# 06-RTL8111H-1.net
KiCad netlist of a schematic drawn in Altium Designer
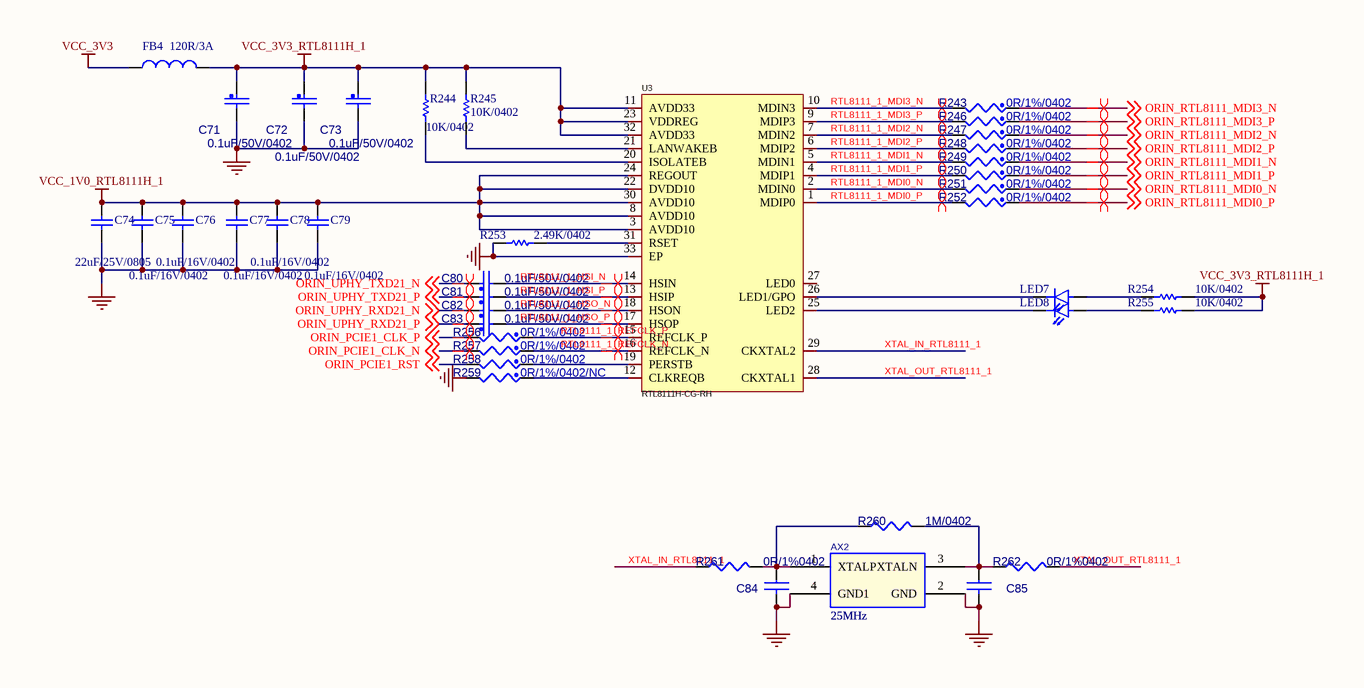
[diagram p0: 06-RTL8111H-1.schdoc]

(export (version "E")
  (design (tool "Eeschema 10.0.6"))
  (components
    (comp (ref "AX2")
      (value "25MHz")
      (footprint "2016")
      (fields (field (name "ALTIUM_VALUE") "25MHz"))
      (libsource (lib "*") (part "XTAL_0"))
    )
    (comp (ref "C71")
      (value "0.1uF/50V/0402")
      (footprint "C0402")
      (description "GCM155R71H104KE02/MURATA")
      (fields (field (name "TOLERANCE") "10%") (field (name "VOLTAGE") "16V"))
      (libsource (lib "*") (part "CAP_NP"))
    )
    (comp (ref "C72")
      (value "0.1uF/50V/0402")
      (footprint "C0402")
      (description "GCM155R71H104KE02/MURATA")
      (fields (field (name "TOLERANCE") "10%") (field (name "VOLTAGE") "16V"))
      (libsource (lib "*") (part "CAP_NP"))
    )
    (comp (ref "C73")
      (value "0.1uF/50V/0402")
      (footprint "C0402")
      (description "GCM155R71H104KE02/MURATA")
      (fields (field (name "TOLERANCE") "10%") (field (name "VOLTAGE") "16V"))
      (libsource (lib "*") (part "CAP_NP"))
    )
    (comp (ref "C74")
      (value "22uF/25V/0805")
      (description "Capacitor")
      (fields (field (name "PUBLISHER") "Altium Limited"))
      (libsource (lib "LIBS") (part "CAP"))
    )
    (comp (ref "C75")
      (value "0.1uF/16V/0402")
      (description "Capacitor")
      (fields (field (name "PUBLISHER") "Altium Limited"))
      (libsource (lib "LIBS") (part "CAP"))
    )
    (comp (ref "C76")
      (value "0.1uF/16V/0402")
      (description "Capacitor")
      (fields (field (name "PUBLISHER") "Altium Limited"))
      (libsource (lib "LIBS") (part "CAP"))
    )
    (comp (ref "C77")
      (value "0.1uF/16V/0402")
      (description "Capacitor")
      (fields (field (name "PUBLISHER") "Altium Limited"))
      (libsource (lib "LIBS") (part "CAP"))
    )
    (comp (ref "C78")
      (value "0.1uF/16V/0402")
      (description "Capacitor")
      (fields (field (name "PUBLISHER") "Altium Limited"))
      (libsource (lib "LIBS") (part "CAP"))
    )
    (comp (ref "C79")
      (value "0.1uF/16V/0402")
      (description "Capacitor")
      (fields (field (name "PUBLISHER") "Altium Limited"))
      (libsource (lib "LIBS") (part "CAP"))
    )
    (comp (ref "C80")
      (value "0.1uF/50V/0402")
      (footprint "C0402")
      (description "GCM155R71H104KE02/MURATA")
      (fields (field (name "TOLERANCE") "10%") (field (name "VOLTAGE") "16V"))
      (libsource (lib "*") (part "CAP_NP"))
    )
    (comp (ref "C81")
      (value "0.1uF/50V/0402")
      (footprint "C0402")
      (description "GCM155R71H104KE02/MURATA")
      (fields (field (name "TOLERANCE") "10%") (field (name "VOLTAGE") "16V"))
      (libsource (lib "*") (part "CAP_NP"))
    )
    (comp (ref "C82")
      (value "0.1uF/50V/0402")
      (footprint "C0402")
      (description "GCM155R71H104KE02/MURATA")
      (fields (field (name "TOLERANCE") "10%") (field (name "VOLTAGE") "16V"))
      (libsource (lib "*") (part "CAP_NP"))
    )
    (comp (ref "C83")
      (value "0.1uF/50V/0402")
      (footprint "C0402")
      (description "GCM155R71H104KE02/MURATA")
      (fields (field (name "TOLERANCE") "10%") (field (name "VOLTAGE") "16V"))
      (libsource (lib "*") (part "CAP_NP"))
    )
    (comp (ref "C84") (value "CAP NP_Dup3") (footprint "C0402") (libsource (lib "*") (part "CAP NP_Dup3")))
    (comp (ref "C85") (value "CAP NP_Dup3") (footprint "C0402") (libsource (lib "*") (part "CAP NP_Dup3")))
    (comp (ref "FB4")
      (value "120R/3A")
      (footprint "L0603")
      (description "BLM18KG121TN1D")
      (fields (field (name "PUBLISHER") "Altium Limited"))
      (libsource (lib "LIBS") (part "Inductor"))
    )
    (comp (ref "LED7") (value "LED_GREEN") (footprint "LED0603") (libsource (lib "LIBS") (part "LED")))
    (comp (ref "LED8") (value "LED_GREEN") (footprint "LED0603") (libsource (lib "LIBS") (part "LED")))
    (comp (ref "R243")
      (value "0R/1%/0402")
      (footprint "R0402")
      (description "AC0402FR-070RL/YAGEO")
      (fields (field (name "TOLERANCE") "1%") (field (name "Comment") "RES_Dup2"))
      (libsource (lib "*") (part "RES_Dup2"))
    )
    (comp (ref "R244")
      (value "10K/0402")
      (footprint "R0402")
      (description "Semiconductor Resistor")
      (fields (field (name "PUBLISHER") "Altium Limited"))
      (libsource (lib "LIBS") (part "Res Semi"))
    )
    (comp (ref "R245")
      (value "10K/0402")
      (footprint "R0402")
      (description "Semiconductor Resistor")
      (fields (field (name "PUBLISHER") "Altium Limited"))
      (libsource (lib "LIBS") (part "Res Semi"))
    )
    (comp (ref "R246")
      (value "0R/1%/0402")
      (footprint "R0402")
      (description "AC0402FR-070RL/YAGEO")
      (fields (field (name "TOLERANCE") "1%") (field (name "Comment") "RES_Dup2"))
      (libsource (lib "*") (part "RES_Dup2"))
    )
    (comp (ref "R247")
      (value "0R/1%/0402")
      (footprint "R0402")
      (description "AC0402FR-070RL/YAGEO")
      (fields (field (name "TOLERANCE") "1%") (field (name "Comment") "RES_Dup2"))
      (libsource (lib "*") (part "RES_Dup2"))
    )
    (comp (ref "R248")
      (value "0R/1%/0402")
      (footprint "R0402")
      (description "AC0402FR-070RL/YAGEO")
      (fields (field (name "TOLERANCE") "1%") (field (name "Comment") "RES_Dup2"))
      (libsource (lib "*") (part "RES_Dup2"))
    )
    (comp (ref "R249")
      (value "0R/1%/0402")
      (footprint "R0402")
      (description "AC0402FR-070RL/YAGEO")
      (fields (field (name "TOLERANCE") "1%") (field (name "Comment") "RES_Dup2"))
      (libsource (lib "*") (part "RES_Dup2"))
    )
    (comp (ref "R250")
      (value "0R/1%/0402")
      (footprint "R0402")
      (description "AC0402FR-070RL/YAGEO")
      (fields (field (name "TOLERANCE") "1%") (field (name "Comment") "RES_Dup2"))
      (libsource (lib "*") (part "RES_Dup2"))
    )
    (comp (ref "R251")
      (value "0R/1%/0402")
      (footprint "R0402")
      (description "AC0402FR-070RL/YAGEO")
      (fields (field (name "TOLERANCE") "1%") (field (name "Comment") "RES_Dup2"))
      (libsource (lib "*") (part "RES_Dup2"))
    )
    (comp (ref "R252")
      (value "0R/1%/0402")
      (footprint "R0402")
      (description "AC0402FR-070RL/YAGEO")
      (fields (field (name "TOLERANCE") "1%") (field (name "Comment") "RES_Dup2"))
      (libsource (lib "*") (part "RES_Dup2"))
    )
    (comp (ref "R253")
      (value "2.49K/0402")
      (footprint "R0402")
      (description "Semiconductor Resistor")
      (fields (field (name "PUBLISHER") "Altium Limited"))
      (libsource (lib "LIBS") (part "Res Semi"))
    )
    (comp (ref "R254")
      (value "10K/0402")
      (footprint "R0402")
      (description "Semiconductor Resistor")
      (fields (field (name "PUBLISHER") "Altium Limited"))
      (libsource (lib "LIBS") (part "Res Semi"))
    )
    (comp (ref "R255")
      (value "10K/0402")
      (footprint "R0402")
      (description "Semiconductor Resistor")
      (fields (field (name "PUBLISHER") "Altium Limited"))
      (libsource (lib "LIBS") (part "Res Semi"))
    )
    (comp (ref "R256")
      (value "0R/1%/0402")
      (footprint "R0402")
      (description "AC0402FR-070RL/YAGEO")
      (fields (field (name "TOLERANCE") "1%") (field (name "Comment") "RES_Dup2"))
      (libsource (lib "*") (part "RES_Dup2"))
    )
    (comp (ref "R257")
      (value "0R/1%/0402")
      (footprint "R0402")
      (description "AC0402FR-070RL/YAGEO")
      (fields (field (name "TOLERANCE") "1%") (field (name "Comment") "RES_Dup2"))
      (libsource (lib "*") (part "RES_Dup2"))
    )
    (comp (ref "R258")
      (value "0R/1%/0402")
      (footprint "R0402")
      (description "AC0402FR-070RL/YAGEO")
      (fields (field (name "TOLERANCE") "1%") (field (name "Comment") "RES_Dup2"))
      (libsource (lib "*") (part "RES_Dup2"))
    )
    (comp (ref "R259")
      (value "0R/1%/0402/NC")
      (footprint "R0402")
      (description "AC0402FR-070RL/YAGEO")
      (fields (field (name "TOLERANCE") "1%") (field (name "Comment") "RES_Dup2"))
      (libsource (lib "*") (part "RES_Dup2"))
    )
    (comp (ref "R260")
      (value "1M/0402")
      (footprint "R0402")
      (fields (field (name "Comment") "R_Dup3"))
      (libsource (lib "*") (part "R_Dup3"))
    )
    (comp (ref "R261")
      (value "0R/1%0402")
      (footprint "R0402")
      (fields (field (name "Comment") "R_Dup3"))
      (libsource (lib "*") (part "R_Dup3"))
    )
    (comp (ref "R262")
      (value "0R/1%0402")
      (footprint "R0402")
      (fields (field (name "Comment") "R_Dup3"))
      (libsource (lib "*") (part "R_Dup3"))
    )
    (comp (ref "U3")
      (value "RTL8111H-CG-RH")
      (footprint "RTL8111H-CG-RH")
      (fields (field (name "MANUFACTURER") "REALTEK(瑞昱)") (field (name "MANUFACTURER PART") "RTL8111H-CG"))
      (libsource (lib "17267508141_1726750814") (part "RTL8111H-CG"))
    )
  )
  (nets
    (net (code "1") (name "/RTL8111_1_HSI_N") (class "Default")
      (node (ref "C80") (pin "2") (pinfunction "2_2") (pintype "passive"))
      (node (ref "U3") (pin "14") (pinfunction "HSIN_14") (pintype "passive"))
    )
    (net (code "2") (name "/RTL8111_1_HSI_P") (class "Default")
      (node (ref "C81") (pin "2") (pinfunction "2_2") (pintype "passive"))
      (node (ref "U3") (pin "13") (pinfunction "HSIP_13") (pintype "passive"))
    )
    (net (code "3") (name "/RTL8111_1_HSO_N") (class "Default")
      (node (ref "C82") (pin "2") (pinfunction "2_2") (pintype "passive"))
      (node (ref "U3") (pin "18") (pinfunction "HSON_18") (pintype "passive"))
    )
    (net (code "4") (name "/RTL8111_1_HSO_P") (class "Default")
      (node (ref "C83") (pin "2") (pinfunction "2_2") (pintype "passive"))
      (node (ref "U3") (pin "17") (pinfunction "HSOP_17") (pintype "passive"))
    )
    (net (code "5") (name "/RTL8111_1_MDI0_N") (class "Default")
      (node (ref "R251") (pin "2") (pinfunction "2_2") (pintype "passive"))
      (node (ref "U3") (pin "2") (pinfunction "MDIN0_2") (pintype "passive"))
    )
    (net (code "6") (name "/RTL8111_1_MDI0_P") (class "Default")
      (node (ref "R252") (pin "2") (pinfunction "2_2") (pintype "passive"))
      (node (ref "U3") (pin "1") (pinfunction "MDIP0_1") (pintype "passive"))
    )
    (net (code "7") (name "/RTL8111_1_MDI1_N") (class "Default")
      (node (ref "R249") (pin "2") (pinfunction "2_2") (pintype "passive"))
      (node (ref "U3") (pin "5") (pinfunction "MDIN1_5") (pintype "passive"))
    )
    (net (code "8") (name "/RTL8111_1_MDI1_P") (class "Default")
      (node (ref "R250") (pin "2") (pinfunction "2_2") (pintype "passive"))
      (node (ref "U3") (pin "4") (pinfunction "MDIP1_4") (pintype "passive"))
    )
    (net (code "9") (name "/RTL8111_1_MDI2_N") (class "Default")
      (node (ref "R247") (pin "2") (pinfunction "2_2") (pintype "passive"))
      (node (ref "U3") (pin "7") (pinfunction "MDIN2_7") (pintype "passive"))
    )
    (net (code "10") (name "/RTL8111_1_MDI2_P") (class "Default")
      (node (ref "R248") (pin "2") (pinfunction "2_2") (pintype "passive"))
      (node (ref "U3") (pin "6") (pinfunction "MDIP2_6") (pintype "passive"))
    )
    (net (code "11") (name "/RTL8111_1_MDI3_N") (class "Default")
      (node (ref "R243") (pin "2") (pinfunction "2_2") (pintype "passive"))
      (node (ref "U3") (pin "10") (pinfunction "MDIN3_10") (pintype "passive"))
    )
    (net (code "12") (name "/RTL8111_1_MDI3_P") (class "Default")
      (node (ref "R246") (pin "2") (pinfunction "2_2") (pintype "passive"))
      (node (ref "U3") (pin "9") (pinfunction "MDIP3_9") (pintype "passive"))
    )
    (net (code "13") (name "/RTL8111_1_REFCLK_N") (class "Default")
      (node (ref "R257") (pin "1") (pinfunction "1_1") (pintype "passive"))
      (node (ref "U3") (pin "16") (pinfunction "REFCLK_N_16") (pintype "passive"))
    )
    (net (code "14") (name "/RTL8111_1_REFCLK_P") (class "Default")
      (node (ref "R256") (pin "1") (pinfunction "1_1") (pintype "passive"))
      (node (ref "U3") (pin "15") (pinfunction "REFCLK_P_15") (pintype "passive"))
    )
    (net (code "15") (name "/XTAL_IN_RTL8111_1") (class "Default")
      (node (ref "R261") (pin "1") (pinfunction "1_1") (pintype "passive"))
      (node (ref "U3") (pin "29") (pinfunction "CKXTAL2_29") (pintype "passive"))
    )
    (net (code "16") (name "/XTAL_OUT_RTL8111_1") (class "Default")
      (node (ref "R262") (pin "2") (pinfunction "2_2") (pintype "passive"))
      (node (ref "U3") (pin "28") (pinfunction "CKXTAL1_28") (pintype "passive"))
    )
    (net (code "17") (name "GND") (class "Default")
      (node (ref "AX2") (pin "2") (pinfunction "GND_2") (pintype "passive"))
      (node (ref "AX2") (pin "4") (pinfunction "GND1_4") (pintype "passive"))
      (node (ref "C71") (pin "2") (pinfunction "2_2") (pintype "passive"))
      (node (ref "C72") (pin "2") (pinfunction "2_2") (pintype "passive"))
      (node (ref "C73") (pin "2") (pinfunction "2_2") (pintype "passive"))
      (node (ref "C74") (pin "1") (pinfunction "1_1") (pintype "passive"))
      (node (ref "C75") (pin "1") (pinfunction "1_1") (pintype "passive"))
      (node (ref "C76") (pin "1") (pinfunction "1_1") (pintype "passive"))
      (node (ref "C77") (pin "1") (pinfunction "1_1") (pintype "passive"))
      (node (ref "C78") (pin "1") (pinfunction "1_1") (pintype "passive"))
      (node (ref "C79") (pin "1") (pinfunction "1_1") (pintype "passive"))
      (node (ref "C84") (pin "2") (pinfunction "2_2") (pintype "passive"))
      (node (ref "C85") (pin "2") (pinfunction "2_2") (pintype "passive"))
      (node (ref "R253") (pin "1") (pinfunction "1_1") (pintype "passive"))
      (node (ref "R259") (pin "2") (pinfunction "2_2") (pintype "passive"))
      (node (ref "U3") (pin "33") (pinfunction "EP_33") (pintype "passive"))
    )
    (net (code "18") (name "Net-(AX2-XTALN)") (class "Default")
      (node (ref "AX2") (pin "3") (pinfunction "XTALN_3") (pintype "passive"))
      (node (ref "C85") (pin "1") (pinfunction "1_1") (pintype "passive"))
      (node (ref "R260") (pin "2") (pinfunction "2_2") (pintype "passive"))
      (node (ref "R262") (pin "1") (pinfunction "1_1") (pintype "passive"))
    )
    (net (code "19") (name "Net-(AX2-XTALP)") (class "Default")
      (node (ref "AX2") (pin "1") (pinfunction "XTALP_1") (pintype "passive"))
      (node (ref "C84") (pin "1") (pinfunction "1_1") (pintype "passive"))
      (node (ref "R260") (pin "1") (pinfunction "1_1") (pintype "passive"))
      (node (ref "R261") (pin "2") (pinfunction "2_2") (pintype "passive"))
    )
    (net (code "20") (name "Net-(LED7-Pad1)") (class "Default")
      (node (ref "LED7") (pin "1") (pinfunction "1_1") (pintype "passive"))
      (node (ref "R254") (pin "2") (pinfunction "2_2") (pintype "passive"))
    )
    (net (code "21") (name "Net-(LED8-Pad1)") (class "Default")
      (node (ref "LED8") (pin "1") (pinfunction "1_1") (pintype "passive"))
      (node (ref "R255") (pin "2") (pinfunction "2_2") (pintype "passive"))
    )
    (net (code "22") (name "Net-(U3-CLKREQB)") (class "Default")
      (node (ref "R259") (pin "1") (pinfunction "1_1") (pintype "passive"))
      (node (ref "U3") (pin "12") (pinfunction "CLKREQB_12") (pintype "passive"))
    )
    (net (code "23") (name "Net-(U3-ISOLATEB)") (class "Default")
      (node (ref "R244") (pin "2") (pinfunction "2_2") (pintype "passive"))
      (node (ref "U3") (pin "20") (pinfunction "ISOLATEB_20") (pintype "passive"))
    )
    (net (code "24") (name "Net-(U3-LANWAKEB)") (class "Default")
      (node (ref "R245") (pin "2") (pinfunction "2_2") (pintype "passive"))
      (node (ref "U3") (pin "21") (pinfunction "LANWAKEB_21") (pintype "passive"))
    )
    (net (code "25") (name "Net-(U3-LED1{slash}GPO)") (class "Default")
      (node (ref "LED7") (pin "2") (pinfunction "2_2") (pintype "passive"))
      (node (ref "U3") (pin "26") (pinfunction "LED1/GPO_26") (pintype "passive"))
    )
    (net (code "26") (name "Net-(U3-LED2)") (class "Default")
      (node (ref "LED8") (pin "2") (pinfunction "2_2") (pintype "passive"))
      (node (ref "U3") (pin "25") (pinfunction "LED2_25") (pintype "passive"))
    )
    (net (code "27") (name "Net-(U3-PERSTB)") (class "Default")
      (node (ref "R258") (pin "1") (pinfunction "1_1") (pintype "passive"))
      (node (ref "U3") (pin "19") (pinfunction "PERSTB_19") (pintype "passive"))
    )
    (net (code "28") (name "Net-(U3-RSET)") (class "Default")
      (node (ref "R253") (pin "2") (pinfunction "2_2") (pintype "passive"))
      (node (ref "U3") (pin "31") (pinfunction "RSET_31") (pintype "passive"))
    )
    (net (code "29") (name "ORIN_PCIE1_CLK_N") (class "Default")
      (node (ref "R257") (pin "2") (pinfunction "2_2") (pintype "passive"))
    )
    (net (code "30") (name "ORIN_PCIE1_CLK_P") (class "Default")
      (node (ref "R256") (pin "2") (pinfunction "2_2") (pintype "passive"))
    )
    (net (code "31") (name "ORIN_PCIE1_RST") (class "Default")
      (node (ref "R258") (pin "2") (pinfunction "2_2") (pintype "passive"))
    )
    (net (code "32") (name "ORIN_RTL8111_MDI0_N") (class "Default")
      (node (ref "R251") (pin "1") (pinfunction "1_1") (pintype "passive"))
    )
    (net (code "33") (name "ORIN_RTL8111_MDI0_P") (class "Default")
      (node (ref "R252") (pin "1") (pinfunction "1_1") (pintype "passive"))
    )
    (net (code "34") (name "ORIN_RTL8111_MDI1_N") (class "Default")
      (node (ref "R249") (pin "1") (pinfunction "1_1") (pintype "passive"))
    )
    (net (code "35") (name "ORIN_RTL8111_MDI1_P") (class "Default")
      (node (ref "R250") (pin "1") (pinfunction "1_1") (pintype "passive"))
    )
    (net (code "36") (name "ORIN_RTL8111_MDI2_N") (class "Default")
      (node (ref "R247") (pin "1") (pinfunction "1_1") (pintype "passive"))
    )
    (net (code "37") (name "ORIN_RTL8111_MDI2_P") (class "Default")
      (node (ref "R248") (pin "1") (pinfunction "1_1") (pintype "passive"))
    )
    (net (code "38") (name "ORIN_RTL8111_MDI3_N") (class "Default")
      (node (ref "R243") (pin "1") (pinfunction "1_1") (pintype "passive"))
    )
    (net (code "39") (name "ORIN_RTL8111_MDI3_P") (class "Default")
      (node (ref "R246") (pin "1") (pinfunction "1_1") (pintype "passive"))
    )
    (net (code "40") (name "ORIN_UPHY_RXD21_N") (class "Default")
      (node (ref "C82") (pin "1") (pinfunction "1_1") (pintype "passive"))
    )
    (net (code "41") (name "ORIN_UPHY_RXD21_P") (class "Default")
      (node (ref "C83") (pin "1") (pinfunction "1_1") (pintype "passive"))
    )
    (net (code "42") (name "ORIN_UPHY_TXD21_N") (class "Default")
      (node (ref "C80") (pin "1") (pinfunction "1_1") (pintype "passive"))
    )
    (net (code "43") (name "ORIN_UPHY_TXD21_P") (class "Default")
      (node (ref "C81") (pin "1") (pinfunction "1_1") (pintype "passive"))
    )
    (net (code "44") (name "VCC_1V0_RTL8111H_1") (class "Default")
      (node (ref "C74") (pin "2") (pinfunction "2_2") (pintype "passive"))
      (node (ref "C75") (pin "2") (pinfunction "2_2") (pintype "passive"))
      (node (ref "C76") (pin "2") (pinfunction "2_2") (pintype "passive"))
      (node (ref "C77") (pin "2") (pinfunction "2_2") (pintype "passive"))
      (node (ref "C78") (pin "2") (pinfunction "2_2") (pintype "passive"))
      (node (ref "C79") (pin "2") (pinfunction "2_2") (pintype "passive"))
      (node (ref "U3") (pin "22") (pinfunction "DVDD10_22") (pintype "passive"))
      (node (ref "U3") (pin "24") (pinfunction "REGOUT_24") (pintype "passive"))
      (node (ref "U3") (pin "3") (pinfunction "AVDD10_3") (pintype "passive"))
      (node (ref "U3") (pin "30") (pinfunction "AVDD10_30") (pintype "passive"))
      (node (ref "U3") (pin "8") (pinfunction "AVDD10_8") (pintype "passive"))
    )
    (net (code "45") (name "VCC_3V3") (class "Default")
      (node (ref "FB4") (pin "1") (pinfunction "1_1") (pintype "passive"))
    )
    (net (code "46") (name "VCC_3V3_RTL8111H_1") (class "Default")
      (node (ref "C71") (pin "1") (pinfunction "1_1") (pintype "passive"))
      (node (ref "C72") (pin "1") (pinfunction "1_1") (pintype "passive"))
      (node (ref "C73") (pin "1") (pinfunction "1_1") (pintype "passive"))
      (node (ref "FB4") (pin "2") (pinfunction "2_2") (pintype "passive"))
      (node (ref "R244") (pin "1") (pinfunction "1_1") (pintype "passive"))
      (node (ref "R245") (pin "1") (pinfunction "1_1") (pintype "passive"))
      (node (ref "R254") (pin "1") (pinfunction "1_1") (pintype "passive"))
      (node (ref "R255") (pin "1") (pinfunction "1_1") (pintype "passive"))
      (node (ref "U3") (pin "11") (pinfunction "AVDD33_11") (pintype "passive"))
      (node (ref "U3") (pin "23") (pinfunction "VDDREG_23") (pintype "passive"))
      (node (ref "U3") (pin "32") (pinfunction "AVDD33_32") (pintype "passive"))
    )
    (net (code "47") (name "unconnected-(U3-LED0-Pad27)") (class "Default")
      (node (ref "U3") (pin "27") (pinfunction "LED0_27") (pintype "passive"))
    )
  )
)
